# main_unit_shield_V1_5.net
KiCad netlist of a schematic drawn in EAGLE
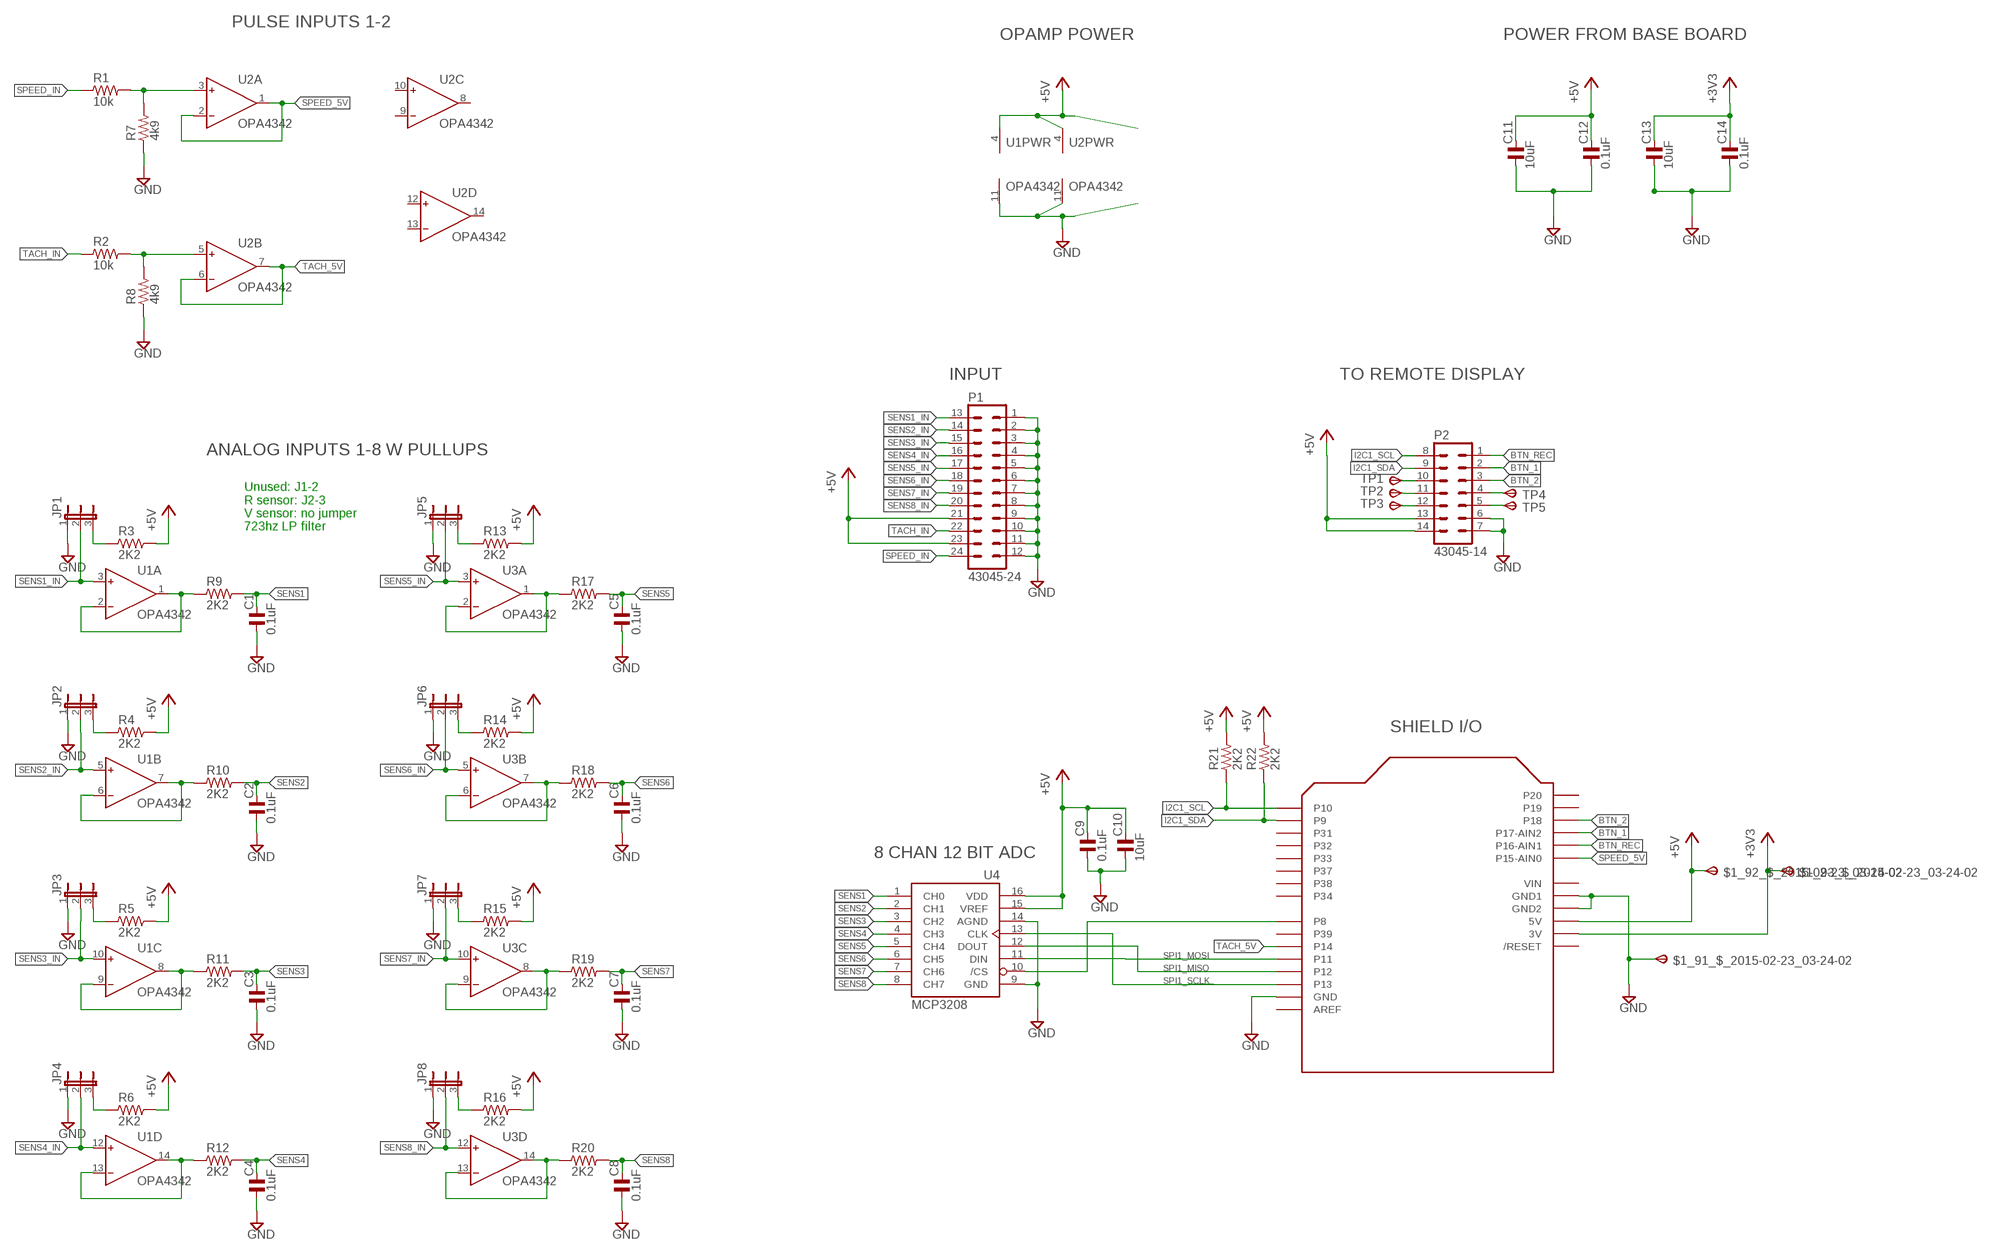
[diagram p0: schematic, sheet 1]

(export (version "E")
  (design (tool "Eeschema 10.0.6"))
  (components
    (comp (ref "$1_91_$_2015-02-23_03-24-02")
      (value "TPSPAD1-13")
      (footprint "eagle-import:P1-13")
      (libsource (lib "eagle-import") (part "TPSPAD1-13"))
    )
    (comp (ref "$1_92_$_2015-02-23_03-24-02")
      (value "TPSPAD1-13")
      (footprint "eagle-import:P1-13")
      (libsource (lib "eagle-import") (part "TPSPAD1-13"))
    )
    (comp (ref "$1_93_$_2015-02-23_03-24-02")
      (value "TPSPAD1-13")
      (footprint "eagle-import:P1-13")
      (libsource (lib "eagle-import") (part "TPSPAD1-13"))
    )
    (comp (ref "C1")
      (value "0.1uF")
      (footprint "eagle-import:C0805")
      (fields (field (name "MPN") "C2012X7R1H104K085AA"))
      (libsource (lib "eagle-import") (part "C_0805"))
    )
    (comp (ref "C2")
      (value "0.1uF")
      (footprint "eagle-import:C0805")
      (fields (field (name "MPN") "C2012X7R1H104K085AA"))
      (libsource (lib "eagle-import") (part "C_0805"))
    )
    (comp (ref "C3")
      (value "0.1uF")
      (footprint "eagle-import:C0805")
      (fields (field (name "MPN") "C2012X7R1H104K085AA"))
      (libsource (lib "eagle-import") (part "C_0805"))
    )
    (comp (ref "C4")
      (value "0.1uF")
      (footprint "eagle-import:C0805")
      (fields (field (name "MPN") "C2012X7R1H104K085AA"))
      (libsource (lib "eagle-import") (part "C_0805"))
    )
    (comp (ref "C5")
      (value "0.1uF")
      (footprint "eagle-import:C0805")
      (fields (field (name "MPN") "C2012X7R1H104K085AA"))
      (libsource (lib "eagle-import") (part "C_0805"))
    )
    (comp (ref "C6")
      (value "0.1uF")
      (footprint "eagle-import:C0805")
      (fields (field (name "MPN") "C2012X7R1H104K085AA"))
      (libsource (lib "eagle-import") (part "C_0805"))
    )
    (comp (ref "C7")
      (value "0.1uF")
      (footprint "eagle-import:C0805")
      (fields (field (name "MPN") "C2012X7R1H104K085AA"))
      (libsource (lib "eagle-import") (part "C_0805"))
    )
    (comp (ref "C8")
      (value "0.1uF")
      (footprint "eagle-import:C0805")
      (fields (field (name "MPN") "C2012X7R1H104K085AA"))
      (libsource (lib "eagle-import") (part "C_0805"))
    )
    (comp (ref "C9")
      (value "0.1uF")
      (footprint "eagle-import:C0805")
      (fields (field (name "MPN") "C2012X7R1H104K085AA"))
      (libsource (lib "eagle-import") (part "C_0805"))
    )
    (comp (ref "C10")
      (value "10uF")
      (footprint "eagle-import:C0805")
      (fields (field (name "MPN") "C2012X5R1E106K125AB"))
      (libsource (lib "eagle-import") (part "C_0805"))
    )
    (comp (ref "C11")
      (value "10uF")
      (footprint "eagle-import:C0805")
      (fields (field (name "MPN") "C2012X5R1E106K125AB"))
      (libsource (lib "eagle-import") (part "C_0805"))
    )
    (comp (ref "C12")
      (value "0.1uF")
      (footprint "eagle-import:C0805")
      (fields (field (name "MPN") "C2012X7R1H104K085AA"))
      (libsource (lib "eagle-import") (part "C_0805"))
    )
    (comp (ref "C13")
      (value "10uF")
      (footprint "eagle-import:C0805")
      (fields (field (name "MPN") "C2012X5R1E106K125AB"))
      (libsource (lib "eagle-import") (part "C_0805"))
    )
    (comp (ref "C14")
      (value "0.1uF")
      (footprint "eagle-import:C0805")
      (fields (field (name "MPN") "C2012X7R1H104K085AA"))
      (libsource (lib "eagle-import") (part "C_0805"))
    )
    (comp (ref "JP1")
      (value "JP2E")
      (footprint "eagle-import:JP2")
      (libsource (lib "eagle-import") (part "JP2E"))
    )
    (comp (ref "JP2")
      (value "JP2E")
      (footprint "eagle-import:JP2")
      (libsource (lib "eagle-import") (part "JP2E"))
    )
    (comp (ref "JP3")
      (value "JP2E")
      (footprint "eagle-import:JP2")
      (libsource (lib "eagle-import") (part "JP2E"))
    )
    (comp (ref "JP4")
      (value "JP2E")
      (footprint "eagle-import:JP2")
      (libsource (lib "eagle-import") (part "JP2E"))
    )
    (comp (ref "JP5")
      (value "JP2E")
      (footprint "eagle-import:JP2")
      (libsource (lib "eagle-import") (part "JP2E"))
    )
    (comp (ref "JP6")
      (value "JP2E")
      (footprint "eagle-import:JP2")
      (libsource (lib "eagle-import") (part "JP2E"))
    )
    (comp (ref "JP7")
      (value "JP2E")
      (footprint "eagle-import:JP2")
      (libsource (lib "eagle-import") (part "JP2E"))
    )
    (comp (ref "JP8")
      (value "JP2E")
      (footprint "eagle-import:JP2")
      (libsource (lib "eagle-import") (part "JP2E"))
    )
    (comp (ref "P1")
      (value "43045-24")
      (footprint "eagle-import:43045-24")
      (fields (field (name "MF") "MOLEX") (field (name "MPN") "43045-2400"))
      (libsource (lib "eagle-import") (part "43045-24"))
    )
    (comp (ref "P2")
      (value "43045-14")
      (footprint "eagle-import:43045-14")
      (fields (field (name "MPN") "43045-1400"))
      (libsource (lib "eagle-import") (part "43045-14"))
    )
    (comp (ref "R1")
      (value "10k")
      (footprint "eagle-import:R0805")
      (fields (field (name "MPN") "CRCW08058K20FKEAHP"))
      (libsource (lib "eagle-import") (part "R_0805"))
    )
    (comp (ref "R2")
      (value "10k")
      (footprint "eagle-import:R0805")
      (fields (field (name "MF") "VISHAY/DALE") (field (name "MPN") "CRCW080520K0FKEA"))
      (libsource (lib "eagle-import") (part "R_0805"))
    )
    (comp (ref "R3")
      (value "2K2")
      (footprint "eagle-import:R0805")
      (fields (field (name "MF") "VISHAY/DALE") (field (name "MPN") "CRCW08052K20FKEA"))
      (libsource (lib "eagle-import") (part "R_0805"))
    )
    (comp (ref "R4")
      (value "2K2")
      (footprint "eagle-import:R0805")
      (fields (field (name "MF") "VISHAY/DALE") (field (name "MPN") "CRCW08052K20FKEA"))
      (libsource (lib "eagle-import") (part "R_0805"))
    )
    (comp (ref "R5")
      (value "2K2")
      (footprint "eagle-import:R0805")
      (fields (field (name "MF") "VISHAY/DALE") (field (name "MPN") "CRCW08052K20FKEA"))
      (libsource (lib "eagle-import") (part "R_0805"))
    )
    (comp (ref "R6")
      (value "2K2")
      (footprint "eagle-import:R0805")
      (fields (field (name "MF") "VISHAY/DALE") (field (name "MPN") "CRCW08052K20FKEA"))
      (libsource (lib "eagle-import") (part "R_0805"))
    )
    (comp (ref "R7")
      (value "4k9")
      (footprint "eagle-import:R0805")
      (fields (field (name "MF") "VISHAY/DALE") (field (name "MPN") "CRCW080520K0FKEA"))
      (libsource (lib "eagle-import") (part "R_0805"))
    )
    (comp (ref "R8")
      (value "4k9")
      (footprint "eagle-import:R0805")
      (fields (field (name "MPN") "CRCW08058K20FKEAHP"))
      (libsource (lib "eagle-import") (part "R_0805"))
    )
    (comp (ref "R9")
      (value "2K2")
      (footprint "eagle-import:R0805")
      (fields (field (name "MF") "VISHAY/DALE") (field (name "MPN") "CRCW08052K20FKEA"))
      (libsource (lib "eagle-import") (part "R_0805"))
    )
    (comp (ref "R10")
      (value "2K2")
      (footprint "eagle-import:R0805")
      (fields (field (name "MF") "VISHAY/DALE") (field (name "MPN") "CRCW08052K20FKEA"))
      (libsource (lib "eagle-import") (part "R_0805"))
    )
    (comp (ref "R11")
      (value "2K2")
      (footprint "eagle-import:R0805")
      (fields (field (name "MF") "VISHAY/DALE") (field (name "MPN") "CRCW08052K20FKEA"))
      (libsource (lib "eagle-import") (part "R_0805"))
    )
    (comp (ref "R12")
      (value "2K2")
      (footprint "eagle-import:R0805")
      (fields (field (name "MF") "VISHAY/DALE") (field (name "MPN") "CRCW08052K20FKEA"))
      (libsource (lib "eagle-import") (part "R_0805"))
    )
    (comp (ref "R13")
      (value "2K2")
      (footprint "eagle-import:R0805")
      (fields (field (name "MF") "VISHAY/DALE") (field (name "MPN") "CRCW08052K20FKEA"))
      (libsource (lib "eagle-import") (part "R_0805"))
    )
    (comp (ref "R14")
      (value "2K2")
      (footprint "eagle-import:R0805")
      (fields (field (name "MF") "VISHAY/DALE") (field (name "MPN") "CRCW08052K20FKEA"))
      (libsource (lib "eagle-import") (part "R_0805"))
    )
    (comp (ref "R15")
      (value "2K2")
      (footprint "eagle-import:R0805")
      (fields (field (name "MF") "VISHAY/DALE") (field (name "MPN") "CRCW08052K20FKEA"))
      (libsource (lib "eagle-import") (part "R_0805"))
    )
    (comp (ref "R16")
      (value "2K2")
      (footprint "eagle-import:R0805")
      (fields (field (name "MF") "VISHAY/DALE") (field (name "MPN") "CRCW08052K20FKEA"))
      (libsource (lib "eagle-import") (part "R_0805"))
    )
    (comp (ref "R17")
      (value "2K2")
      (footprint "eagle-import:R0805")
      (fields (field (name "MF") "VISHAY/DALE") (field (name "MPN") "CRCW08052K20FKEA"))
      (libsource (lib "eagle-import") (part "R_0805"))
    )
    (comp (ref "R18")
      (value "2K2")
      (footprint "eagle-import:R0805")
      (fields (field (name "MF") "VISHAY/DALE") (field (name "MPN") "CRCW08052K20FKEA"))
      (libsource (lib "eagle-import") (part "R_0805"))
    )
    (comp (ref "R19")
      (value "2K2")
      (footprint "eagle-import:R0805")
      (fields (field (name "MF") "VISHAY/DALE") (field (name "MPN") "CRCW08052K20FKEA"))
      (libsource (lib "eagle-import") (part "R_0805"))
    )
    (comp (ref "R20")
      (value "2K2")
      (footprint "eagle-import:R0805")
      (fields (field (name "MF") "VISHAY/DALE") (field (name "MPN") "CRCW08052K20FKEA"))
      (libsource (lib "eagle-import") (part "R_0805"))
    )
    (comp (ref "R21")
      (value "2K2")
      (footprint "eagle-import:R0805")
      (fields (field (name "MF") "VISHAY/DALE") (field (name "MPN") "CRCW08052K20FKEA"))
      (libsource (lib "eagle-import") (part "R_0805"))
    )
    (comp (ref "R22")
      (value "2K2")
      (footprint "eagle-import:R0805")
      (fields (field (name "MF") "VISHAY/DALE") (field (name "MPN") "CRCW08052K20FKEA"))
      (libsource (lib "eagle-import") (part "R_0805"))
    )
    (comp (ref "TP1")
      (value "TPSPAD1-13")
      (footprint "eagle-import:P1-13")
      (libsource (lib "eagle-import") (part "TPSPAD1-13"))
    )
    (comp (ref "TP2")
      (value "TPSPAD1-13")
      (footprint "eagle-import:P1-13")
      (libsource (lib "eagle-import") (part "TPSPAD1-13"))
    )
    (comp (ref "TP3")
      (value "TPSPAD1-13")
      (footprint "eagle-import:P1-13")
      (libsource (lib "eagle-import") (part "TPSPAD1-13"))
    )
    (comp (ref "TP4")
      (value "TPSPAD1-13")
      (footprint "eagle-import:P1-13")
      (libsource (lib "eagle-import") (part "TPSPAD1-13"))
    )
    (comp (ref "TP5")
      (value "TPSPAD1-13")
      (footprint "eagle-import:P1-13")
      (libsource (lib "eagle-import") (part "TPSPAD1-13"))
    )
    (comp (ref "U1")
      (value "OPA4342")
      (footprint "eagle-import:SO14")
      (libsource (lib "eagle-import") (part "OPA4342"))
    )
    (comp (ref "U2")
      (value "OPA4342")
      (footprint "eagle-import:SO14")
      (libsource (lib "eagle-import") (part "OPA4342"))
    )
    (comp (ref "U3")
      (value "OPA4342")
      (footprint "eagle-import:SO14")
      (libsource (lib "eagle-import") (part "OPA4342"))
    )
    (comp (ref "U4")
      (value "MCP3208")
      (footprint "eagle-import:SO16")
      (fields (field (name "MF") "MICROCHIP") (field (name "MPN") "MCP3208-BI/SL"))
      (libsource (lib "eagle-import") (part "MCP3208"))
    )
    (comp (ref "U6")
      (value "ARDUINOUNO")
      (footprint "eagle-import:ARDUINO")
      (libsource (lib "eagle-import") (part "ARDUINOUNO"))
    )
  )
  (nets
    (net (code "1") (name "+3V3") (class "Default")
      (node (ref "$1_93_$_2015-02-23_03-24-02") (pin "TP") (pinfunction "PP_TP") (pintype "input"))
      (node (ref "C13") (pin "2") (pinfunction "2_2") (pintype "passive"))
      (node (ref "C14") (pin "2") (pinfunction "2_2") (pintype "passive"))
      (node (ref "U6") (pin "3V") (pinfunction "3V_3V") (pintype "power_in"))
    )
    (net (code "2") (name "+5V") (class "Default")
      (node (ref "$1_92_$_2015-02-23_03-24-02") (pin "TP") (pinfunction "PP_TP") (pintype "input"))
      (node (ref "C10") (pin "2") (pinfunction "2_2") (pintype "passive"))
      (node (ref "C11") (pin "2") (pinfunction "2_2") (pintype "passive"))
      (node (ref "C12") (pin "2") (pinfunction "2_2") (pintype "passive"))
      (node (ref "C9") (pin "2") (pinfunction "2_2") (pintype "passive"))
      (node (ref "P1") (pin "21") (pinfunction "21_21") (pintype "passive"))
      (node (ref "P1") (pin "23") (pinfunction "23_23") (pintype "passive"))
      (node (ref "P2") (pin "13") (pinfunction "13_13") (pintype "passive"))
      (node (ref "P2") (pin "14") (pinfunction "14_14") (pintype "passive"))
      (node (ref "R13") (pin "2") (pinfunction "2_2") (pintype "passive"))
      (node (ref "R14") (pin "2") (pinfunction "2_2") (pintype "passive"))
      (node (ref "R15") (pin "2") (pinfunction "2_2") (pintype "passive"))
      (node (ref "R16") (pin "2") (pinfunction "2_2") (pintype "passive"))
      (node (ref "R21") (pin "2") (pinfunction "2_2") (pintype "passive"))
      (node (ref "R22") (pin "2") (pinfunction "2_2") (pintype "passive"))
      (node (ref "R3") (pin "2") (pinfunction "2_2") (pintype "passive"))
      (node (ref "R4") (pin "2") (pinfunction "2_2") (pintype "passive"))
      (node (ref "R5") (pin "2") (pinfunction "2_2") (pintype "passive"))
      (node (ref "R6") (pin "2") (pinfunction "2_2") (pintype "passive"))
      (node (ref "U1") (pin "4") (pinfunction "V+_4") (pintype "power_in"))
      (node (ref "U2") (pin "4") (pinfunction "V+_4") (pintype "power_in"))
      (node (ref "U4") (pin "15") (pinfunction "VREF_15") (pintype "input"))
      (node (ref "U4") (pin "16") (pinfunction "VDD_16") (pintype "power_in"))
      (node (ref "U6") (pin "5V") (pinfunction "5V_5V") (pintype "power_in"))
    )
    (net (code "3") (name "/SPI1_MISO") (class "Default")
      (node (ref "U4") (pin "12") (pinfunction "DOUT_12") (pintype "output"))
      (node (ref "U6") (pin "D12") (pinfunction "P12_D12") (pintype "bidirectional"))
    )
    (net (code "4") (name "/SPI1_MOSI") (class "Default")
      (node (ref "U4") (pin "11") (pinfunction "DIN_11") (pintype "input"))
      (node (ref "U6") (pin "D11") (pinfunction "P11_D11") (pintype "bidirectional"))
    )
    (net (code "5") (name "/SPI1_SCLK") (class "Default")
      (node (ref "U4") (pin "13") (pinfunction "CLK_13") (pintype "input"))
      (node (ref "U6") (pin "D13") (pinfunction "P13_D13") (pintype "bidirectional"))
    )
    (net (code "6") (name "/VIN") (class "Default")
      (node (ref "U6") (pin "VIN") (pinfunction "VIN_VIN") (pintype "power_in"))
    )
    (net (code "7") (name "BTN_1") (class "Default")
      (node (ref "P2") (pin "2") (pinfunction "2_2") (pintype "passive"))
      (node (ref "U6") (pin "A2") (pinfunction "P17-AIN2_A2") (pintype "bidirectional"))
    )
    (net (code "8") (name "BTN_2") (class "Default")
      (node (ref "P2") (pin "3") (pinfunction "3_3") (pintype "passive"))
      (node (ref "U6") (pin "A3") (pinfunction "P18_A3") (pintype "bidirectional"))
    )
    (net (code "9") (name "BTN_REC") (class "Default")
      (node (ref "P2") (pin "1") (pinfunction "1_1") (pintype "passive"))
      (node (ref "U6") (pin "A1") (pinfunction "P16-AIN1_A1") (pintype "bidirectional"))
    )
    (net (code "10") (name "GND") (class "Default")
      (node (ref "$1_91_$_2015-02-23_03-24-02") (pin "TP") (pinfunction "PP_TP") (pintype "input"))
      (node (ref "C1") (pin "1") (pinfunction "1_1") (pintype "passive"))
      (node (ref "C10") (pin "1") (pinfunction "1_1") (pintype "passive"))
      (node (ref "C11") (pin "1") (pinfunction "1_1") (pintype "passive"))
      (node (ref "C12") (pin "1") (pinfunction "1_1") (pintype "passive"))
      (node (ref "C13") (pin "1") (pinfunction "1_1") (pintype "passive"))
      (node (ref "C14") (pin "1") (pinfunction "1_1") (pintype "passive"))
      (node (ref "C2") (pin "1") (pinfunction "1_1") (pintype "passive"))
      (node (ref "C3") (pin "1") (pinfunction "1_1") (pintype "passive"))
      (node (ref "C4") (pin "1") (pinfunction "1_1") (pintype "passive"))
      (node (ref "C5") (pin "1") (pinfunction "1_1") (pintype "passive"))
      (node (ref "C6") (pin "1") (pinfunction "1_1") (pintype "passive"))
      (node (ref "C7") (pin "1") (pinfunction "1_1") (pintype "passive"))
      (node (ref "C8") (pin "1") (pinfunction "1_1") (pintype "passive"))
      (node (ref "C9") (pin "1") (pinfunction "1_1") (pintype "passive"))
      (node (ref "JP1") (pin "1") (pinfunction "1_1") (pintype "passive"))
      (node (ref "JP2") (pin "1") (pinfunction "1_1") (pintype "passive"))
      (node (ref "JP3") (pin "1") (pinfunction "1_1") (pintype "passive"))
      (node (ref "JP4") (pin "1") (pinfunction "1_1") (pintype "passive"))
      (node (ref "JP5") (pin "1") (pinfunction "1_1") (pintype "passive"))
      (node (ref "JP6") (pin "1") (pinfunction "1_1") (pintype "passive"))
      (node (ref "JP7") (pin "1") (pinfunction "1_1") (pintype "passive"))
      (node (ref "JP8") (pin "1") (pinfunction "1_1") (pintype "passive"))
      (node (ref "P1") (pin "1") (pinfunction "1_1") (pintype "passive"))
      (node (ref "P1") (pin "10") (pinfunction "10_10") (pintype "passive"))
      (node (ref "P1") (pin "11") (pinfunction "11_11") (pintype "passive"))
      (node (ref "P1") (pin "12") (pinfunction "12_12") (pintype "passive"))
      (node (ref "P1") (pin "2") (pinfunction "2_2") (pintype "passive"))
      (node (ref "P1") (pin "3") (pinfunction "3_3") (pintype "passive"))
      (node (ref "P1") (pin "4") (pinfunction "4_4") (pintype "passive"))
      (node (ref "P1") (pin "5") (pinfunction "5_5") (pintype "passive"))
      (node (ref "P1") (pin "6") (pinfunction "6_6") (pintype "passive"))
      (node (ref "P1") (pin "7") (pinfunction "7_7") (pintype "passive"))
      (node (ref "P1") (pin "8") (pinfunction "8_8") (pintype "passive"))
      (node (ref "P1") (pin "9") (pinfunction "9_9") (pintype "passive"))
      (node (ref "P2") (pin "6") (pinfunction "6_6") (pintype "passive"))
      (node (ref "P2") (pin "7") (pinfunction "7_7") (pintype "passive"))
      (node (ref "R7") (pin "1") (pinfunction "1_1") (pintype "passive"))
      (node (ref "R8") (pin "1") (pinfunction "1_1") (pintype "passive"))
      (node (ref "U1") (pin "11") (pinfunction "V-_11") (pintype "power_in"))
      (node (ref "U2") (pin "11") (pinfunction "V-_11") (pintype "power_in"))
      (node (ref "U4") (pin "14") (pinfunction "AGND_14") (pintype "power_in"))
      (node (ref "U4") (pin "9") (pinfunction "GND_9") (pintype "power_in"))
      (node (ref "U6") (pin "GND") (pinfunction "GND_GND") (pintype "power_in"))
      (node (ref "U6") (pin "GND1") (pinfunction "GND1_GND1") (pintype "power_in"))
      (node (ref "U6") (pin "GND2") (pinfunction "GND2_GND2") (pintype "power_in"))
    )
    (net (code "11") (name "I2C1_SCL") (class "Default")
      (node (ref "P2") (pin "8") (pinfunction "8_8") (pintype "passive"))
      (node (ref "R21") (pin "1") (pinfunction "1_1") (pintype "passive"))
      (node (ref "U6") (pin "D0") (pinfunction "P10_D0") (pintype "bidirectional"))
    )
    (net (code "12") (name "I2C1_SDA") (class "Default")
      (node (ref "P2") (pin "9") (pinfunction "9_9") (pintype "passive"))
      (node (ref "R22") (pin "1") (pinfunction "1_1") (pintype "passive"))
      (node (ref "U6") (pin "D1") (pinfunction "P9_D1") (pintype "bidirectional"))
    )
    (net (code "13") (name "Net-(JP1-Pad3)") (class "Default")
      (node (ref "JP1") (pin "3") (pinfunction "3_3") (pintype "passive"))
      (node (ref "R3") (pin "1") (pinfunction "1_1") (pintype "passive"))
    )
    (net (code "14") (name "Net-(JP2-Pad3)") (class "Default")
      (node (ref "JP2") (pin "3") (pinfunction "3_3") (pintype "passive"))
      (node (ref "R4") (pin "1") (pinfunction "1_1") (pintype "passive"))
    )
    (net (code "15") (name "Net-(JP3-Pad3)") (class "Default")
      (node (ref "JP3") (pin "3") (pinfunction "3_3") (pintype "passive"))
      (node (ref "R5") (pin "1") (pinfunction "1_1") (pintype "passive"))
    )
    (net (code "16") (name "Net-(JP4-Pad3)") (class "Default")
      (node (ref "JP4") (pin "3") (pinfunction "3_3") (pintype "passive"))
      (node (ref "R6") (pin "1") (pinfunction "1_1") (pintype "passive"))
    )
    (net (code "17") (name "Net-(JP5-Pad3)") (class "Default")
      (node (ref "JP5") (pin "3") (pinfunction "3_3") (pintype "passive"))
      (node (ref "R13") (pin "1") (pinfunction "1_1") (pintype "passive"))
    )
    (net (code "18") (name "Net-(JP6-Pad3)") (class "Default")
      (node (ref "JP6") (pin "3") (pinfunction "3_3") (pintype "passive"))
      (node (ref "R14") (pin "1") (pinfunction "1_1") (pintype "passive"))
    )
    (net (code "19") (name "Net-(JP7-Pad3)") (class "Default")
      (node (ref "JP7") (pin "3") (pinfunction "3_3") (pintype "passive"))
      (node (ref "R15") (pin "1") (pinfunction "1_1") (pintype "passive"))
    )
    (net (code "20") (name "Net-(JP8-Pad3)") (class "Default")
      (node (ref "JP8") (pin "3") (pinfunction "3_3") (pintype "passive"))
      (node (ref "R16") (pin "1") (pinfunction "1_1") (pintype "passive"))
    )
    (net (code "21") (name "Net-(TP1-PP)") (class "Default")
      (node (ref "P2") (pin "10") (pinfunction "10_10") (pintype "passive"))
      (node (ref "TP1") (pin "TP") (pinfunction "PP_TP") (pintype "input"))
    )
    (net (code "22") (name "Net-(TP2-PP)") (class "Default")
      (node (ref "P2") (pin "11") (pinfunction "11_11") (pintype "passive"))
      (node (ref "TP2") (pin "TP") (pinfunction "PP_TP") (pintype "input"))
    )
    (net (code "23") (name "Net-(TP3-PP)") (class "Default")
      (node (ref "P2") (pin "12") (pinfunction "12_12") (pintype "passive"))
      (node (ref "TP3") (pin "TP") (pinfunction "PP_TP") (pintype "input"))
    )
    (net (code "24") (name "Net-(TP4-PP)") (class "Default")
      (node (ref "P2") (pin "4") (pinfunction "4_4") (pintype "passive"))
      (node (ref "TP4") (pin "TP") (pinfunction "PP_TP") (pintype "input"))
    )
    (net (code "25") (name "Net-(TP5-PP)") (class "Default")
      (node (ref "P2") (pin "5") (pinfunction "5_5") (pintype "passive"))
      (node (ref "TP5") (pin "TP") (pinfunction "PP_TP") (pintype "input"))
    )
    (net (code "26") (name "Net-(U1A-IN-)") (class "Default")
      (node (ref "R9") (pin "1") (pinfunction "1_1") (pintype "passive"))
      (node (ref "U1") (pin "1") (pinfunction "OUT_1") (pintype "output"))
      (node (ref "U1") (pin "2") (pinfunction "IN-_2") (pintype "input"))
    )
    (net (code "27") (name "Net-(U1B-IN-)") (class "Default")
      (node (ref "R10") (pin "1") (pinfunction "1_1") (pintype "passive"))
      (node (ref "U1") (pin "6") (pinfunction "IN-_6") (pintype "input"))
      (node (ref "U1") (pin "7") (pinfunction "OUT_7") (pintype "output"))
    )
    (net (code "28") (name "Net-(U1C-IN-)") (class "Default")
      (node (ref "R11") (pin "1") (pinfunction "1_1") (pintype "passive"))
      (node (ref "U1") (pin "8") (pinfunction "OUT_8") (pintype "output"))
      (node (ref "U1") (pin "9") (pinfunction "IN-_9") (pintype "input"))
    )
    (net (code "29") (name "Net-(U1D-IN-)") (class "Default")
      (node (ref "R12") (pin "1") (pinfunction "1_1") (pintype "passive"))
      (node (ref "U1") (pin "13") (pinfunction "IN-_13") (pintype "input"))
      (node (ref "U1") (pin "14") (pinfunction "OUT_14") (pintype "output"))
    )
    (net (code "30") (name "Net-(U2A-IN+)") (class "Default")
      (node (ref "R1") (pin "2") (pinfunction "2_2") (pintype "passive"))
      (node (ref "R7") (pin "2") (pinfunction "2_2") (pintype "passive"))
      (node (ref "U2") (pin "3") (pinfunction "IN+_3") (pintype "input"))
    )
    (net (code "31") (name "Net-(U2B-IN+)") (class "Default")
      (node (ref "R2") (pin "2") (pinfunction "2_2") (pintype "passive"))
      (node (ref "R8") (pin "2") (pinfunction "2_2") (pintype "passive"))
      (node (ref "U2") (pin "5") (pinfunction "IN+_5") (pintype "input"))
    )
    (net (code "32") (name "Net-(U3A-IN-)") (class "Default")
      (node (ref "R17") (pin "1") (pinfunction "1_1") (pintype "passive"))
      (node (ref "U3") (pin "1") (pinfunction "OUT_1") (pintype "output"))
      (node (ref "U3") (pin "2") (pinfunction "IN-_2") (pintype "input"))
    )
    (net (code "33") (name "Net-(U3B-IN-)") (class "Default")
      (node (ref "R18") (pin "1") (pinfunction "1_1") (pintype "passive"))
      (node (ref "U3") (pin "6") (pinfunction "IN-_6") (pintype "input"))
      (node (ref "U3") (pin "7") (pinfunction "OUT_7") (pintype "output"))
    )
    (net (code "34") (name "Net-(U3C-IN-)") (class "Default")
      (node (ref "R19") (pin "1") (pinfunction "1_1") (pintype "passive"))
      (node (ref "U3") (pin "8") (pinfunction "OUT_8") (pintype "output"))
      (node (ref "U3") (pin "9") (pinfunction "IN-_9") (pintype "input"))
    )
    (net (code "35") (name "Net-(U3D-IN-)") (class "Default")
      (node (ref "R20") (pin "1") (pinfunction "1_1") (pintype "passive"))
      (node (ref "U3") (pin "13") (pinfunction "IN-_13") (pintype "input"))
      (node (ref "U3") (pin "14") (pinfunction "OUT_14") (pintype "output"))
    )
    (net (code "36") (name "Net-(U4-{slash}CS)") (class "Default")
      (node (ref "U4") (pin "10") (pinfunction "/CS_10") (pintype "input"))
      (node (ref "U6") (pin "D8") (pinfunction "P8_D8") (pintype "bidirectional"))
    )
    (net (code "37") (name "SENS1") (class "Default")
      (node (ref "C1") (pin "2") (pinfunction "2_2") (pintype "passive"))
      (node (ref "R9") (pin "2") (pinfunction "2_2") (pintype "passive"))
      (node (ref "U4") (pin "1") (pinfunction "CH0_1") (pintype "input"))
    )
    (net (code "38") (name "SENS1_IN") (class "Default")
      (node (ref "JP1") (pin "2") (pinfunction "2_2") (pintype "passive"))
      (node (ref "P1") (pin "13") (pinfunction "13_13") (pintype "passive"))
      (node (ref "U1") (pin "3") (pinfunction "IN+_3") (pintype "input"))
    )
    (net (code "39") (name "SENS2") (class "Default")
      (node (ref "C2") (pin "2") (pinfunction "2_2") (pintype "passive"))
      (node (ref "R10") (pin "2") (pinfunction "2_2") (pintype "passive"))
      (node (ref "U4") (pin "2") (pinfunction "CH1_2") (pintype "input"))
    )
    (net (code "40") (name "SENS2_IN") (class "Default")
      (node (ref "JP2") (pin "2") (pinfunction "2_2") (pintype "passive"))
      (node (ref "P1") (pin "14") (pinfunction "14_14") (pintype "passive"))
      (node (ref "U1") (pin "5") (pinfunction "IN+_5") (pintype "input"))
    )
    (net (code "41") (name "SENS3") (class "Default")
      (node (ref "C3") (pin "2") (pinfunction "2_2") (pintype "passive"))
      (node (ref "R11") (pin "2") (pinfunction "2_2") (pintype "passive"))
      (node (ref "U4") (pin "3") (pinfunction "CH2_3") (pintype "input"))
    )
    (net (code "42") (name "SENS3_IN") (class "Default")
      (node (ref "JP3") (pin "2") (pinfunction "2_2") (pintype "passive"))
      (node (ref "P1") (pin "15") (pinfunction "15_15") (pintype "passive"))
      (node (ref "U1") (pin "10") (pinfunction "IN+_10") (pintype "input"))
    )
    (net (code "43") (name "SENS4") (class "Default")
      (node (ref "C4") (pin "2") (pinfunction "2_2") (pintype "passive"))
      (node (ref "R12") (pin "2") (pinfunction "2_2") (pintype "passive"))
      (node (ref "U4") (pin "4") (pinfunction "CH3_4") (pintype "input"))
    )
    (net (code "44") (name "SENS4_IN") (class "Default")
      (node (ref "JP4") (pin "2") (pinfunction "2_2") (pintype "passive"))
      (node (ref "P1") (pin "16") (pinfunction "16_16") (pintype "passive"))
      (node (ref "U1") (pin "12") (pinfunction "IN+_12") (pintype "input"))
    )
    (net (code "45") (name "SENS5") (class "Default")
      (node (ref "C5") (pin "2") (pinfunction "2_2") (pintype "passive"))
      (node (ref "R17") (pin "2") (pinfunction "2_2") (pintype "passive"))
      (node (ref "U4") (pin "5") (pinfunction "CH4_5") (pintype "input"))
    )
    (net (code "46") (name "SENS5_IN") (class "Default")
      (node (ref "JP5") (pin "2") (pinfunction "2_2") (pintype "passive"))
      (node (ref "P1") (pin "17") (pinfunction "17_17") (pintype "passive"))
      (node (ref "U3") (pin "3") (pinfunction "IN+_3") (pintype "input"))
    )
    (net (code "47") (name "SENS6") (class "Default")
      (node (ref "C6") (pin "2") (pinfunction "2_2") (pintype "passive"))
      (node (ref "R18") (pin "2") (pinfunction "2_2") (pintype "passive"))
      (node (ref "U4") (pin "6") (pinfunction "CH5_6") (pintype "input"))
    )
    (net (code "48") (name "SENS6_IN") (class "Default")
      (node (ref "JP6") (pin "2") (pinfunction "2_2") (pintype "passive"))
      (node (ref "P1") (pin "18") (pinfunction "18_18") (pintype "passive"))
      (node (ref "U3") (pin "5") (pinfunction "IN+_5") (pintype "input"))
    )
    (net (code "49") (name "SENS7") (class "Default")
      (node (ref "C7") (pin "2") (pinfunction "2_2") (pintype "passive"))
      (node (ref "R19") (pin "2") (pinfunction "2_2") (pintype "passive"))
      (node (ref "U4") (pin "7") (pinfunction "CH6_7") (pintype "input"))
    )
    (net (code "50") (name "SENS7_IN") (class "Default")
      (node (ref "JP7") (pin "2") (pinfunction "2_2") (pintype "passive"))
      (node (ref "P1") (pin "19") (pinfunction "19_19") (pintype "passive"))
      (node (ref "U3") (pin "10") (pinfunction "IN+_10") (pintype "input"))
    )
    (net (code "51") (name "SENS8") (class "Default")
      (node (ref "C8") (pin "2") (pinfunction "2_2") (pintype "passive"))
      (node (ref "R20") (pin "2") (pinfunction "2_2") (pintype "passive"))
      (node (ref "U4") (pin "8") (pinfunction "CH7_8") (pintype "input"))
    )
    (net (code "52") (name "SENS8_IN") (class "Default")
      (node (ref "JP8") (pin "2") (pinfunction "2_2") (pintype "passive"))
      (node (ref "P1") (pin "20") (pinfunction "20_20") (pintype "passive"))
      (node (ref "U3") (pin "12") (pinfunction "IN+_12") (pintype "input"))
    )
    (net (code "53") (name "SPEED_5V") (class "Default")
      (node (ref "U2") (pin "1") (pinfunction "OUT_1") (pintype "output"))
      (node (ref "U2") (pin "2") (pinfunction "IN-_2") (pintype "input"))
      (node (ref "U6") (pin "A0") (pinfunction "P15-AIN0_A0") (pintype "bidirectional"))
    )
    (net (code "54") (name "SPEED_IN") (class "Default")
      (node (ref "P1") (pin "24") (pinfunction "24_24") (pintype "passive"))
      (node (ref "R1") (pin "1") (pinfunction "1_1") (pintype "passive"))
    )
    (net (code "55") (name "TACH_5V") (class "Default")
      (node (ref "U2") (pin "6") (pinfunction "IN-_6") (pintype "input"))
      (node (ref "U2") (pin "7") (pinfunction "OUT_7") (pintype "output"))
      (node (ref "U6") (pin "D10") (pinfunction "P14_D10") (pintype "bidirectional"))
    )
    (net (code "56") (name "TACH_IN") (class "Default")
      (node (ref "P1") (pin "22") (pinfunction "22_22") (pintype "passive"))
      (node (ref "R2") (pin "1") (pinfunction "1_1") (pintype "passive"))
    )
    (net (code "57") (name "unconnected-(U2C-IN+-Pad10)") (class "Default")
      (node (ref "U2") (pin "10") (pinfunction "IN+_10") (pintype "input"))
    )
    (net (code "58") (name "unconnected-(U2C-IN--Pad9)") (class "Default")
      (node (ref "U2") (pin "9") (pinfunction "IN-_9") (pintype "input"))
    )
    (net (code "59") (name "unconnected-(U2C-OUT-Pad8)") (class "Default")
      (node (ref "U2") (pin "8") (pinfunction "OUT_8") (pintype "output"))
    )
    (net (code "60") (name "unconnected-(U2D-IN+-Pad12)") (class "Default")
      (node (ref "U2") (pin "12") (pinfunction "IN+_12") (pintype "input"))
    )
    (net (code "61") (name "unconnected-(U2D-IN--Pad13)") (class "Default")
      (node (ref "U2") (pin "13") (pinfunction "IN-_13") (pintype "input"))
    )
    (net (code "62") (name "unconnected-(U2D-OUT-Pad14)") (class "Default")
      (node (ref "U2") (pin "14") (pinfunction "OUT_14") (pintype "output"))
    )
    (net (code "63") (name "unconnected-(U6-P19-PadA4)") (class "Default")
      (node (ref "U6") (pin "A4") (pinfunction "P19_A4") (pintype "bidirectional"))
    )
    (net (code "64") (name "unconnected-(U6-P20-PadA5)") (class "Default")
      (node (ref "U6") (pin "A5") (pinfunction "P20_A5") (pintype "bidirectional"))
    )
    (net (code "65") (name "unconnected-(U6-P31-PadD2)") (class "Default")
      (node (ref "U6") (pin "D2") (pinfunction "P31_D2") (pintype "bidirectional"))
    )
    (net (code "66") (name "unconnected-(U6-P32-PadD3)") (class "Default")
      (node (ref "U6") (pin "D3") (pinfunction "P32_D3") (pintype "bidirectional"))
    )
    (net (code "67") (name "unconnected-(U6-P33-PadD4)") (class "Default")
      (node (ref "U6") (pin "D4") (pinfunction "P33_D4") (pintype "bidirectional"))
    )
    (net (code "68") (name "unconnected-(U6-P34-PadD7)") (class "Default")
      (node (ref "U6") (pin "D7") (pinfunction "P34_D7") (pintype "bidirectional"))
    )
    (net (code "69") (name "unconnected-(U6-P37-PadD5)") (class "Default")
      (node (ref "U6") (pin "D5") (pinfunction "P37_D5") (pintype "bidirectional"))
    )
    (net (code "70") (name "unconnected-(U6-P38-PadD6)") (class "Default")
      (node (ref "U6") (pin "D6") (pinfunction "P38_D6") (pintype "bidirectional"))
    )
    (net (code "71") (name "unconnected-(U6-P39-PadD9)") (class "Default")
      (node (ref "U6") (pin "D9") (pinfunction "P39_D9") (pintype "bidirectional"))
    )
    (net (code "72") (name "unconnected-(U6-PadAREF)") (class "Default")
      (node (ref "U6") (pin "AREF") (pinfunction "AREF_AREF") (pintype "bidirectional"))
    )
    (net (code "73") (name "unconnected-(U6-{slash}RESET-PadRESET)") (class "Default")
      (node (ref "U6") (pin "RESET") (pinfunction "/RESET_RESET") (pintype "bidirectional"))
    )
  )
)
